# M_2_E-KEY.net
KiCad netlist of a schematic drawn in Altium Designer
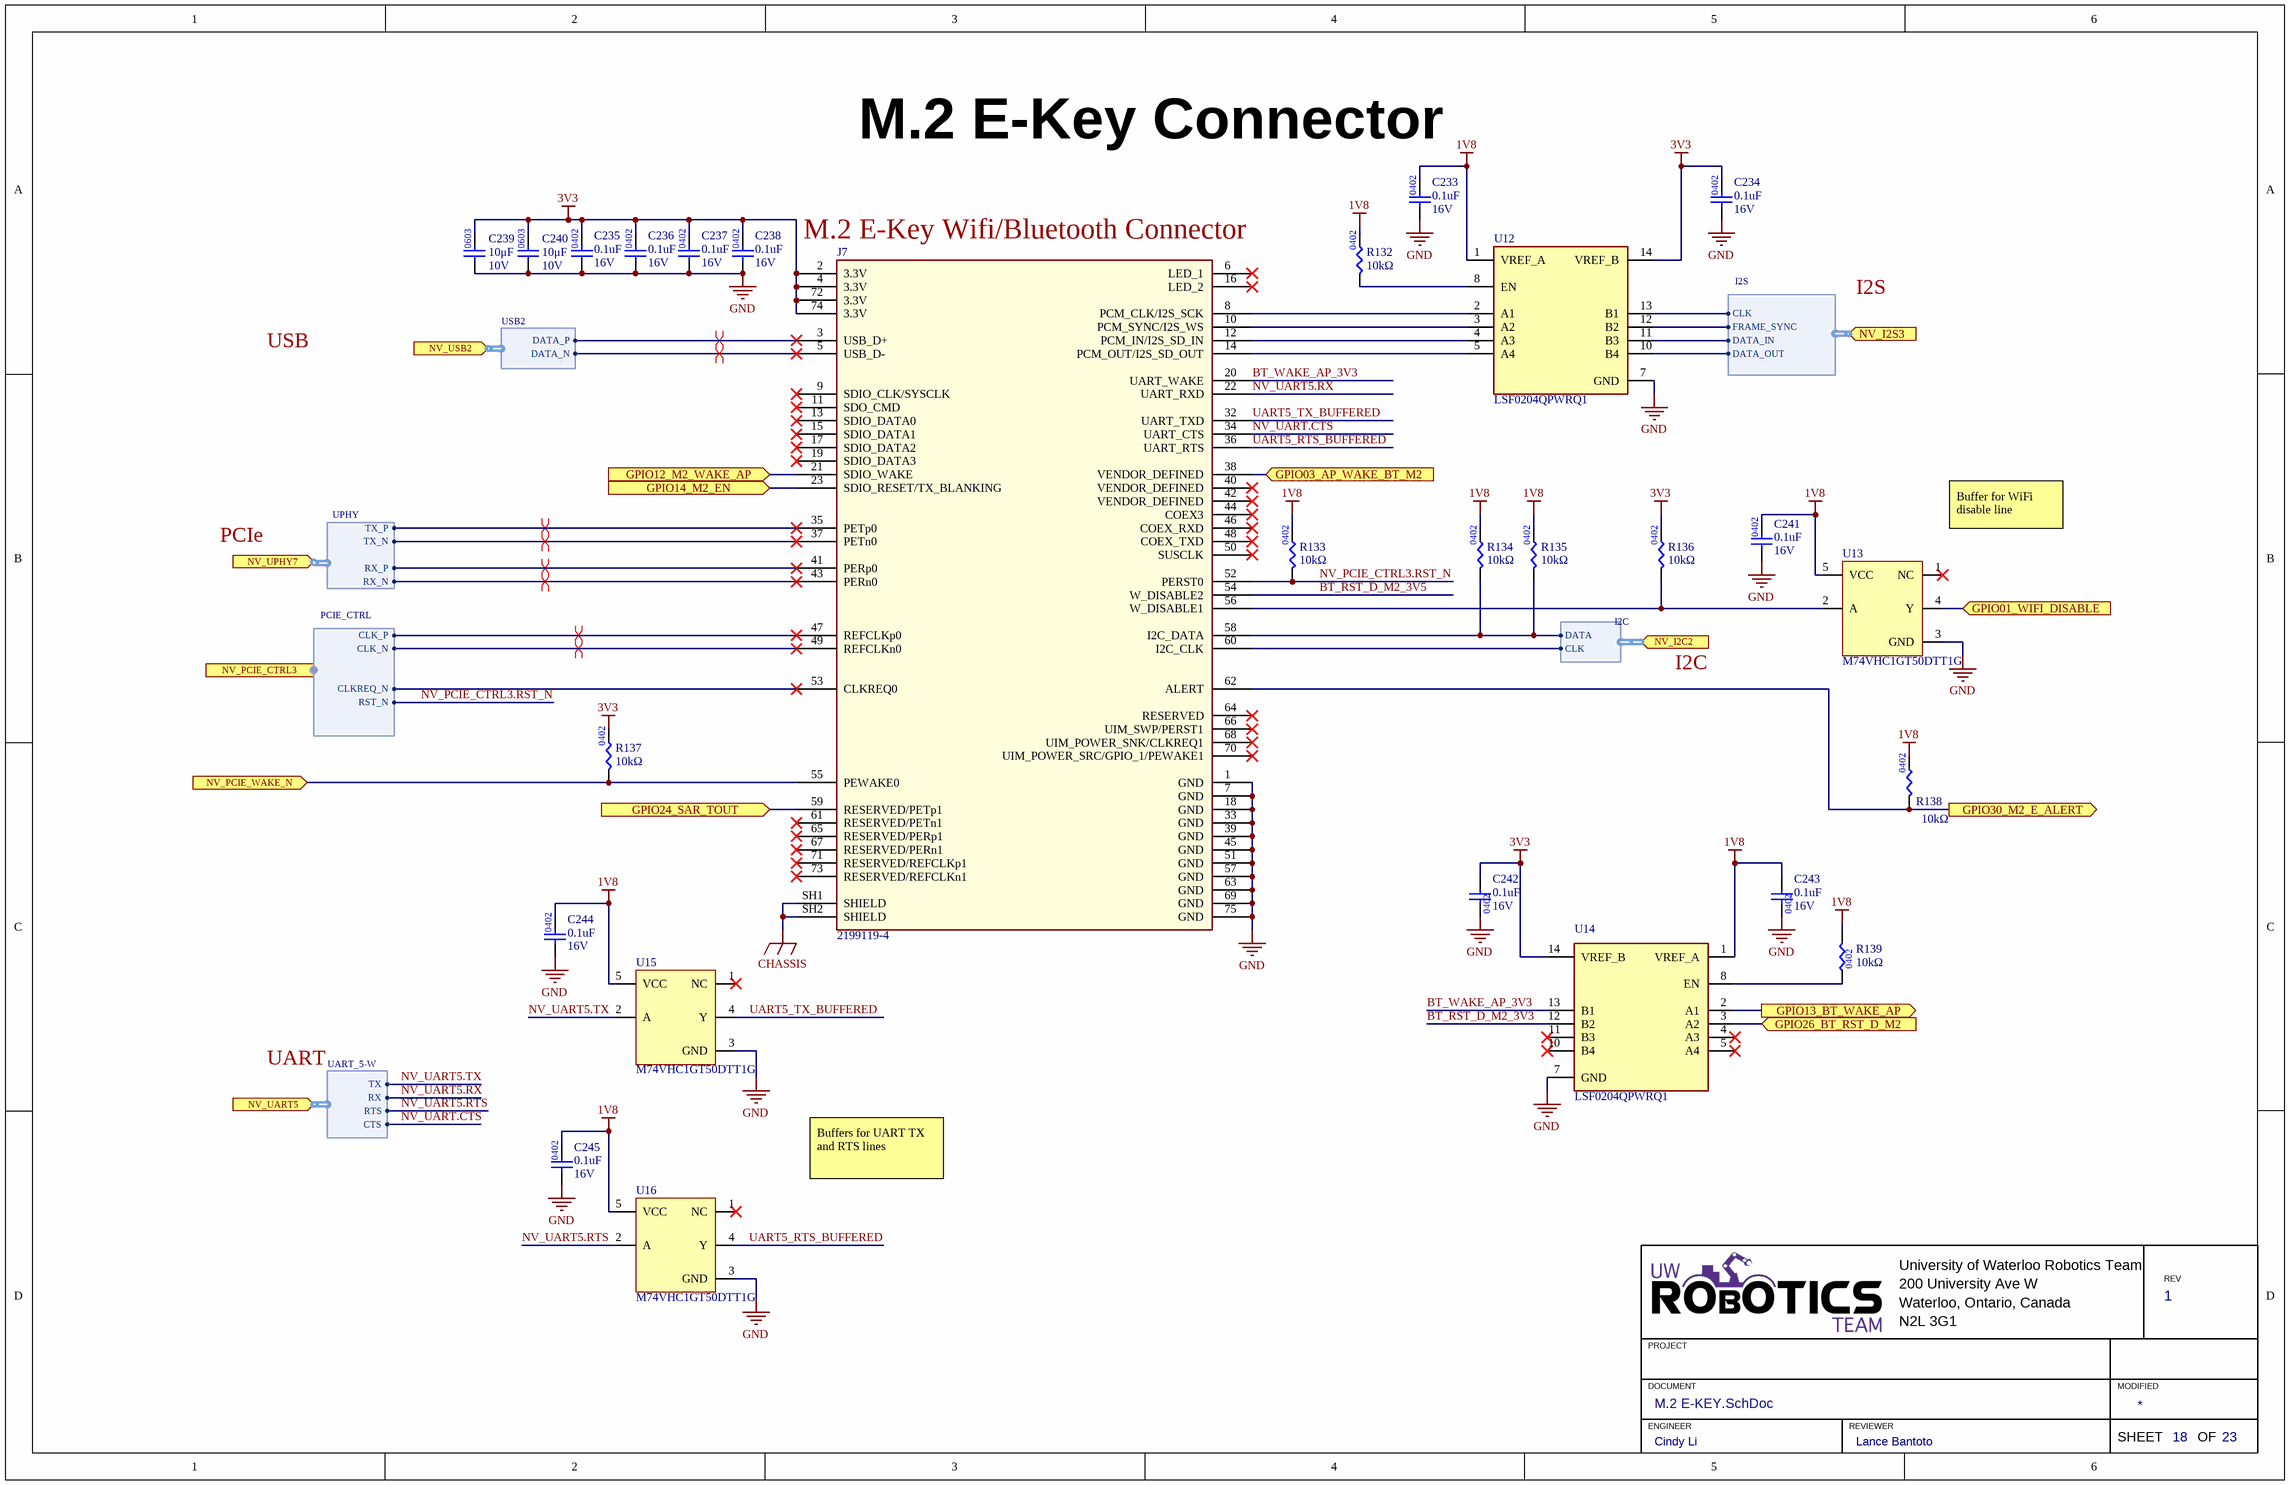
[diagram p0: M.2 E-KEY.SchDoc]

(export (version "E")
  (design (tool "Eeschema 10.0.6"))
  (components
    (comp (ref "C233")
      (value "CAP_0.1uF_16V_X7R_0402")
      (footprint "CAP0402")
      (description "CAP CER 0.1UF 16V X7R 0402")
      (fields (field (name "CAPACITANCE") "0.1uF") (field (name "VOLTAGE RATING") "16V"))
      (libsource (lib "UWRT_Schematic_Library_2020") (part "CAP_0.1uF_16V_X7R_0402"))
    )
    (comp (ref "C234")
      (value "CAP_0.1uF_16V_X7R_0402")
      (footprint "CAP0402")
      (description "CAP CER 0.1UF 16V X7R 0402")
      (fields (field (name "CAPACITANCE") "0.1uF") (field (name "VOLTAGE RATING") "16V"))
      (libsource (lib "UWRT_Schematic_Library_2020") (part "CAP_0.1uF_16V_X7R_0402"))
    )
    (comp (ref "C235")
      (value "CAP_0.1uF_16V_X7R_0402")
      (footprint "CAP0402")
      (description "CAP CER 0.1UF 16V X7R 0402")
      (fields (field (name "CAPACITANCE") "0.1uF") (field (name "VOLTAGE RATING") "16V"))
      (libsource (lib "UWRT_Schematic_Library_2020") (part "CAP_0.1uF_16V_X7R_0402"))
    )
    (comp (ref "C236")
      (value "CAP_0.1uF_16V_X7R_0402")
      (footprint "CAP0402")
      (description "CAP CER 0.1UF 16V X7R 0402")
      (fields (field (name "CAPACITANCE") "0.1uF") (field (name "VOLTAGE RATING") "16V"))
      (libsource (lib "UWRT_Schematic_Library_2020") (part "CAP_0.1uF_16V_X7R_0402"))
    )
    (comp (ref "C237")
      (value "CAP_0.1uF_16V_X7R_0402")
      (footprint "CAP0402")
      (description "CAP CER 0.1UF 16V X7R 0402")
      (fields (field (name "CAPACITANCE") "0.1uF") (field (name "VOLTAGE RATING") "16V"))
      (libsource (lib "UWRT_Schematic_Library_2020") (part "CAP_0.1uF_16V_X7R_0402"))
    )
    (comp (ref "C238")
      (value "CAP_0.1uF_16V_X7R_0402")
      (footprint "CAP0402")
      (description "CAP CER 0.1UF 16V X7R 0402")
      (fields (field (name "CAPACITANCE") "0.1uF") (field (name "VOLTAGE RATING") "16V"))
      (libsource (lib "UWRT_Schematic_Library_2020") (part "CAP_0.1uF_16V_X7R_0402"))
    )
    (comp (ref "C239")
      (value "10μF")
      (footprint "CAP0603")
      (description "CAP CER 10UF 10V X5R 0603")
      (fields (field (name "VOLTAGE RATING") "10V") (field (name "Comment") "CAP_10uF_10V_0603"))
      (libsource (lib "UWRT_Schematic_Library_2020") (part "CAP_10uF_10V_0603"))
    )
    (comp (ref "C240")
      (value "10μF")
      (footprint "CAP0603")
      (description "CAP CER 10UF 10V X5R 0603")
      (fields (field (name "VOLTAGE RATING") "10V") (field (name "Comment") "CAP_10uF_10V_0603"))
      (libsource (lib "UWRT_Schematic_Library_2020") (part "CAP_10uF_10V_0603"))
    )
    (comp (ref "C241")
      (value "CAP_0.1uF_16V_X7R_0402")
      (footprint "CAP0402")
      (description "CAP CER 0.1UF 16V X7R 0402")
      (fields (field (name "CAPACITANCE") "0.1uF") (field (name "VOLTAGE RATING") "16V"))
      (libsource (lib "UWRT_Schematic_Library_2020") (part "CAP_0.1uF_16V_X7R_0402"))
    )
    (comp (ref "C242")
      (value "CAP_0.1uF_16V_X7R_0402")
      (footprint "CAP0402")
      (description "CAP CER 0.1UF 16V X7R 0402")
      (fields (field (name "CAPACITANCE") "0.1uF") (field (name "VOLTAGE RATING") "16V"))
      (libsource (lib "UWRT_Schematic_Library_2020") (part "CAP_0.1uF_16V_X7R_0402"))
    )
    (comp (ref "C243")
      (value "CAP_0.1uF_16V_X7R_0402")
      (footprint "CAP0402")
      (description "CAP CER 0.1UF 16V X7R 0402")
      (fields (field (name "CAPACITANCE") "0.1uF") (field (name "VOLTAGE RATING") "16V"))
      (libsource (lib "UWRT_Schematic_Library_2020") (part "CAP_0.1uF_16V_X7R_0402"))
    )
    (comp (ref "C244")
      (value "CAP_0.1uF_16V_X7R_0402")
      (footprint "CAP0402")
      (description "CAP CER 0.1UF 16V X7R 0402")
      (fields (field (name "CAPACITANCE") "0.1uF") (field (name "VOLTAGE RATING") "16V"))
      (libsource (lib "UWRT_Schematic_Library_2020") (part "CAP_0.1uF_16V_X7R_0402"))
    )
    (comp (ref "C245")
      (value "CAP_0.1uF_16V_X7R_0402")
      (footprint "CAP0402")
      (description "CAP CER 0.1UF 16V X7R 0402")
      (fields (field (name "CAPACITANCE") "0.1uF") (field (name "VOLTAGE RATING") "16V"))
      (libsource (lib "UWRT_Schematic_Library_2020") (part "CAP_0.1uF_16V_X7R_0402"))
    )
    (comp (ref "J7")
      (value "2199119-4")
      (footprint "TE_2199119-4")
      (description "CONN M.2 FEMALE 67POS 0.020 GOLD")
      (fields (field (name "MANUFACTURER PART NUMBER 1") "2199119-4"))
      (libsource (lib "UWRT_Schematic_Library_2020") (part "2199119-4"))
    )
    (comp (ref "R132")
      (value "RES_10kΩ_0402_1%")
      (footprint "RES0402")
      (description "RES 10K OHM 1% 1/16W 0402")
      (fields (field (name "TOLERANCE") "1%") (field (name "RESISTANCE") "10kΩ"))
      (libsource (lib "UWRT_Schematic_Library_2020") (part "RES_10kΩ_0402_1%"))
    )
    (comp (ref "R133")
      (value "RES_10kΩ_0402_1%")
      (footprint "RES0402")
      (description "RES 10K OHM 1% 1/16W 0402")
      (fields (field (name "TOLERANCE") "1%") (field (name "RESISTANCE") "10kΩ"))
      (libsource (lib "UWRT_Schematic_Library_2020") (part "RES_10kΩ_0402_1%"))
    )
    (comp (ref "R134")
      (value "RES_10kΩ_0402_1%")
      (footprint "RES0402")
      (description "RES 10K OHM 1% 1/16W 0402")
      (fields (field (name "TOLERANCE") "1%") (field (name "RESISTANCE") "10kΩ"))
      (libsource (lib "UWRT_Schematic_Library_2020") (part "RES_10kΩ_0402_1%"))
    )
    (comp (ref "R135")
      (value "RES_10kΩ_0402_1%")
      (footprint "RES0402")
      (description "RES 10K OHM 1% 1/16W 0402")
      (fields (field (name "TOLERANCE") "1%") (field (name "RESISTANCE") "10kΩ"))
      (libsource (lib "UWRT_Schematic_Library_2020") (part "RES_10kΩ_0402_1%"))
    )
    (comp (ref "R136")
      (value "RES_10kΩ_0402_1%")
      (footprint "RES0402")
      (description "RES 10K OHM 1% 1/16W 0402")
      (fields (field (name "TOLERANCE") "1%") (field (name "RESISTANCE") "10kΩ"))
      (libsource (lib "UWRT_Schematic_Library_2020") (part "RES_10kΩ_0402_1%"))
    )
    (comp (ref "R137")
      (value "RES_10kΩ_0402_1%")
      (footprint "RES0402")
      (description "RES 10K OHM 1% 1/16W 0402")
      (fields (field (name "TOLERANCE") "1%") (field (name "RESISTANCE") "10kΩ"))
      (libsource (lib "UWRT_Schematic_Library_2020") (part "RES_10kΩ_0402_1%"))
    )
    (comp (ref "R138")
      (value "RES_10kΩ_0402_1%")
      (footprint "RES0402")
      (description "RES 10K OHM 1% 1/16W 0402")
      (fields (field (name "TOLERANCE") "1%") (field (name "RESISTANCE") "10kΩ"))
      (libsource (lib "UWRT_Schematic_Library_2020") (part "RES_10kΩ_0402_1%"))
    )
    (comp (ref "R139")
      (value "RES_10kΩ_0402_1%")
      (footprint "RES0402")
      (description "RES 10K OHM 1% 1/16W 0402")
      (fields (field (name "TOLERANCE") "1%") (field (name "RESISTANCE") "10kΩ"))
      (libsource (lib "UWRT_Schematic_Library_2020") (part "RES_10kΩ_0402_1%"))
    )
    (comp (ref "U12")
      (value "LSF0204QPWRQ1")
      (footprint "14-TSSOP")
      (description "4-BITS MULTI-VOLTAGE LEVEL TRANS")
      (libsource (lib "UWRT_Schematic_Library_2020") (part "LSF0204QPWRQ1"))
    )
    (comp (ref "U13")
      (value "IC_BUFFER")
      (footprint "SOT23-5")
      (description "IC BUFFER NON-INVERT 5.5V 5TSOP")
      (fields (field (name "MANUFACTURER PART NUMBER 1") "M74VHC1GT50DTT1G"))
      (libsource (lib "UWRT_Schematic_Library_2020") (part "IC_BUFFER"))
    )
    (comp (ref "U14")
      (value "LSF0204QPWRQ1")
      (footprint "14-TSSOP")
      (description "4-BITS MULTI-VOLTAGE LEVEL TRANS")
      (libsource (lib "") (part "LSF0204QPWRQ1_1"))
    )
    (comp (ref "U15")
      (value "IC_BUFFER")
      (footprint "SOT23-5")
      (description "IC BUFFER NON-INVERT 5.5V 5TSOP")
      (fields (field (name "MANUFACTURER PART NUMBER 1") "M74VHC1GT50DTT1G"))
      (libsource (lib "UWRT_Schematic_Library_2020") (part "IC_BUFFER"))
    )
    (comp (ref "U16")
      (value "IC_BUFFER")
      (footprint "SOT23-5")
      (description "IC BUFFER NON-INVERT 5.5V 5TSOP")
      (fields (field (name "MANUFACTURER PART NUMBER 1") "M74VHC1GT50DTT1G"))
      (libsource (lib "UWRT_Schematic_Library_2020") (part "IC_BUFFER"))
    )
  )
  (nets
    (net (code "7") (name "/BT_RST_D_M2_3V3") (class "Default")
      (node (ref "U14") (pin "12") (pinfunction "B2_12") (pintype "passive"))
    )
    (net (code "8") (name "/BT_RST_D_M2_3V5") (class "Default")
      (node (ref "J7") (pin "54") (pinfunction "W_DISABLE2_54") (pintype "passive"))
    )
    (net (code "9") (name "/BT_WAKE_AP_3V3") (class "Default")
      (node (ref "J7") (pin "20") (pinfunction "UART_WAKE_20") (pintype "passive"))
      (node (ref "U14") (pin "13") (pinfunction "B1_13") (pintype "passive"))
    )
    (net (code "10") (name "/CLKREQ_N") (class "Default")
      (node (ref "J7") (pin "53") (pinfunction "CLKREQ0_53") (pintype "passive+no_connect"))
    )
    (net (code "11") (name "/CLK_N") (class "Default")
      (node (ref "J7") (pin "49") (pinfunction "REFCLKn0_49") (pintype "passive+no_connect"))
    )
    (net (code "12") (name "/CLK_P") (class "Default")
      (node (ref "J7") (pin "47") (pinfunction "REFCLKp0_47") (pintype "passive+no_connect"))
    )
    (net (code "13") (name "/DATA") (class "Default")
      (node (ref "J7") (pin "58") (pinfunction "I2C_DATA_58") (pintype "passive"))
      (node (ref "R134") (pin "1") (pinfunction "1_1") (pintype "passive"))
      (node (ref "R135") (pin "1") (pinfunction "1_1") (pintype "passive"))
    )
    (net (code "14") (name "/DATA_IN") (class "Default")
      (node (ref "U12") (pin "11") (pinfunction "B3_11") (pintype "passive"))
    )
    (net (code "15") (name "/DATA_N") (class "Default")
      (node (ref "J7") (pin "5") (pinfunction "USB_D-_5") (pintype "passive+no_connect"))
    )
    (net (code "16") (name "/DATA_OUT") (class "Default")
      (node (ref "U12") (pin "10") (pinfunction "B4_10") (pintype "passive"))
    )
    (net (code "17") (name "/DATA_P") (class "Default")
      (node (ref "J7") (pin "3") (pinfunction "USB_D+_3") (pintype "passive+no_connect"))
    )
    (net (code "18") (name "/FRAME_SYNC") (class "Default")
      (node (ref "U12") (pin "12") (pinfunction "B2_12") (pintype "passive"))
    )
    (net (code "19") (name "/GPIO01_WIFI_DISABLE") (class "Default")
      (node (ref "U13") (pin "4") (pinfunction "Y_4") (pintype "passive"))
    )
    (net (code "20") (name "/GPIO03_AP_WAKE_BT_M2") (class "Default")
      (node (ref "J7") (pin "38") (pinfunction "VENDOR_DEFINED_38") (pintype "passive"))
    )
    (net (code "21") (name "/GPIO12_M2_WAKE_AP") (class "Default")
      (node (ref "J7") (pin "21") (pinfunction "SDIO_WAKE_21") (pintype "passive"))
    )
    (net (code "22") (name "/GPIO13_BT_WAKE_AP") (class "Default")
      (node (ref "U14") (pin "2") (pinfunction "A1_2") (pintype "passive"))
    )
    (net (code "23") (name "/GPIO14_M2_EN") (class "Default")
      (node (ref "J7") (pin "23") (pinfunction "SDIO_RESET/TX_BLANKING_23") (pintype "passive"))
    )
    (net (code "24") (name "/GPIO24_SAR_TOUT") (class "Default")
      (node (ref "J7") (pin "59") (pinfunction "RESERVED/PETp1_59") (pintype "passive"))
    )
    (net (code "25") (name "/GPIO26_BT_RST_D_M2") (class "Default")
      (node (ref "U14") (pin "3") (pinfunction "A2_3") (pintype "passive"))
    )
    (net (code "26") (name "/GPIO30_M2_E_ALERT") (class "Default")
      (node (ref "J7") (pin "62") (pinfunction "ALERT_62") (pintype "passive"))
      (node (ref "R138") (pin "1") (pinfunction "1_1") (pintype "passive"))
    )
    (net (code "27") (name "/NV_PCIE_CTRL3.RST_N") (class "Default")
      (node (ref "J7") (pin "52") (pinfunction "PERST0_52") (pintype "passive"))
      (node (ref "R133") (pin "1") (pinfunction "1_1") (pintype "passive"))
    )
    (net (code "28") (name "/NV_PCIE_WAKE_N") (class "Default")
      (node (ref "J7") (pin "55") (pinfunction "PEWAKE0_55") (pintype "passive"))
      (node (ref "R137") (pin "1") (pinfunction "1_1") (pintype "passive"))
    )
    (net (code "29") (name "/NV_UART.CTS") (class "Default")
      (node (ref "J7") (pin "34") (pinfunction "UART_CTS_34") (pintype "passive"))
    )
    (net (code "30") (name "/NV_UART5.RTS") (class "Default")
      (node (ref "U16") (pin "2") (pinfunction "A_2") (pintype "passive"))
    )
    (net (code "31") (name "/NV_UART5.RX") (class "Default")
      (node (ref "J7") (pin "22") (pinfunction "UART_RXD_22") (pintype "passive"))
    )
    (net (code "32") (name "/NV_UART5.TX") (class "Default")
      (node (ref "U15") (pin "2") (pinfunction "A_2") (pintype "passive"))
    )
    (net (code "33") (name "/RX_N") (class "Default")
      (node (ref "J7") (pin "43") (pinfunction "PERn0_43") (pintype "passive+no_connect"))
    )
    (net (code "34") (name "/RX_P") (class "Default")
      (node (ref "J7") (pin "41") (pinfunction "PERp0_41") (pintype "passive+no_connect"))
    )
    (net (code "35") (name "/TX_N") (class "Default")
      (node (ref "J7") (pin "37") (pinfunction "PETn0_37") (pintype "passive+no_connect"))
    )
    (net (code "36") (name "/TX_P") (class "Default")
      (node (ref "J7") (pin "35") (pinfunction "PETp0_35") (pintype "passive+no_connect"))
    )
    (net (code "37") (name "/UART5_RTS_BUFFERED") (class "Default")
      (node (ref "J7") (pin "36") (pinfunction "UART_RTS_36") (pintype "passive"))
      (node (ref "U16") (pin "4") (pinfunction "Y_4") (pintype "passive"))
    )
    (net (code "38") (name "/UART5_TX_BUFFERED") (class "Default")
      (node (ref "J7") (pin "32") (pinfunction "UART_TXD_32") (pintype "passive"))
      (node (ref "U15") (pin "4") (pinfunction "Y_4") (pintype "passive"))
    )
    (net (code "45") (name "1V8") (class "Default")
      (node (ref "C233") (pin "2") (pinfunction "2_2") (pintype "passive"))
      (node (ref "C241") (pin "2") (pinfunction "2_2") (pintype "passive"))
      (node (ref "C243") (pin "2") (pinfunction "2_2") (pintype "passive"))
      (node (ref "C244") (pin "2") (pinfunction "2_2") (pintype "passive"))
      (node (ref "C245") (pin "2") (pinfunction "2_2") (pintype "passive"))
      (node (ref "R132") (pin "2") (pinfunction "2_2") (pintype "passive"))
      (node (ref "R133") (pin "2") (pinfunction "2_2") (pintype "passive"))
      (node (ref "R134") (pin "2") (pinfunction "2_2") (pintype "passive"))
      (node (ref "R135") (pin "2") (pinfunction "2_2") (pintype "passive"))
      (node (ref "R138") (pin "2") (pinfunction "2_2") (pintype "passive"))
      (node (ref "R139") (pin "2") (pinfunction "2_2") (pintype "passive"))
      (node (ref "U12") (pin "1") (pinfunction "VREF_A_1") (pintype "passive"))
      (node (ref "U13") (pin "5") (pinfunction "VCC_5") (pintype "passive"))
      (node (ref "U14") (pin "1") (pinfunction "VREF_A_1") (pintype "passive"))
      (node (ref "U15") (pin "5") (pinfunction "VCC_5") (pintype "passive"))
      (node (ref "U16") (pin "5") (pinfunction "VCC_5") (pintype "passive"))
    )
    (net (code "46") (name "3V3") (class "Default")
      (node (ref "C234") (pin "2") (pinfunction "2_2") (pintype "passive"))
      (node (ref "C235") (pin "2") (pinfunction "2_2") (pintype "passive"))
      (node (ref "C236") (pin "2") (pinfunction "2_2") (pintype "passive"))
      (node (ref "C237") (pin "2") (pinfunction "2_2") (pintype "passive"))
      (node (ref "C238") (pin "2") (pinfunction "2_2") (pintype "passive"))
      (node (ref "C239") (pin "2") (pinfunction "2_2") (pintype "passive"))
      (node (ref "C240") (pin "2") (pinfunction "2_2") (pintype "passive"))
      (node (ref "C242") (pin "2") (pinfunction "2_2") (pintype "passive"))
      (node (ref "J7") (pin "2") (pinfunction "3.3V_2") (pintype "passive"))
      (node (ref "J7") (pin "4") (pinfunction "3.3V_4") (pintype "passive"))
      (node (ref "J7") (pin "72") (pinfunction "3.3V_72") (pintype "passive"))
      (node (ref "J7") (pin "74") (pinfunction "3.3V_74") (pintype "passive"))
      (node (ref "R136") (pin "2") (pinfunction "2_2") (pintype "passive"))
      (node (ref "R137") (pin "2") (pinfunction "2_2") (pintype "passive"))
      (node (ref "U12") (pin "14") (pinfunction "VREF_B_14") (pintype "passive"))
      (node (ref "U14") (pin "14") (pinfunction "VREF_B_14") (pintype "passive"))
    )
    (net (code "47") (name "CHASSIS") (class "Default")
      (node (ref "J7") (pin "SH1") (pinfunction "SHIELD_SH1") (pintype "passive"))
      (node (ref "J7") (pin "SH2") (pinfunction "SHIELD_SH2") (pintype "passive"))
    )
    (net (code "48") (name "GND") (class "Default")
      (node (ref "C233") (pin "1") (pinfunction "1_1") (pintype "passive"))
      (node (ref "C234") (pin "1") (pinfunction "1_1") (pintype "passive"))
      (node (ref "C235") (pin "1") (pinfunction "1_1") (pintype "passive"))
      (node (ref "C236") (pin "1") (pinfunction "1_1") (pintype "passive"))
      (node (ref "C237") (pin "1") (pinfunction "1_1") (pintype "passive"))
      (node (ref "C238") (pin "1") (pinfunction "1_1") (pintype "passive"))
      (node (ref "C239") (pin "1") (pinfunction "1_1") (pintype "passive"))
      (node (ref "C240") (pin "1") (pinfunction "1_1") (pintype "passive"))
      (node (ref "C241") (pin "1") (pinfunction "1_1") (pintype "passive"))
      (node (ref "C242") (pin "1") (pinfunction "1_1") (pintype "passive"))
      (node (ref "C243") (pin "1") (pinfunction "1_1") (pintype "passive"))
      (node (ref "C244") (pin "1") (pinfunction "1_1") (pintype "passive"))
      (node (ref "C245") (pin "1") (pinfunction "1_1") (pintype "passive"))
      (node (ref "J7") (pin "1") (pinfunction "GND_1") (pintype "passive"))
      (node (ref "J7") (pin "18") (pinfunction "GND_18") (pintype "passive"))
      (node (ref "J7") (pin "33") (pinfunction "GND_33") (pintype "passive"))
      (node (ref "J7") (pin "39") (pinfunction "GND_39") (pintype "passive"))
      (node (ref "J7") (pin "45") (pinfunction "GND_45") (pintype "passive"))
      (node (ref "J7") (pin "51") (pinfunction "GND_51") (pintype "passive"))
      (node (ref "J7") (pin "57") (pinfunction "GND_57") (pintype "passive"))
      (node (ref "J7") (pin "63") (pinfunction "GND_63") (pintype "passive"))
      (node (ref "J7") (pin "69") (pinfunction "GND_69") (pintype "passive"))
      (node (ref "J7") (pin "7") (pinfunction "GND_7") (pintype "passive"))
      (node (ref "J7") (pin "75") (pinfunction "GND_75") (pintype "passive"))
      (node (ref "U12") (pin "7") (pinfunction "GND_7") (pintype "passive"))
      (node (ref "U13") (pin "3") (pinfunction "GND_3") (pintype "passive"))
      (node (ref "U14") (pin "7") (pinfunction "GND_7") (pintype "passive"))
      (node (ref "U15") (pin "3") (pinfunction "GND_3") (pintype "passive"))
      (node (ref "U16") (pin "3") (pinfunction "GND_3") (pintype "passive"))
    )
    (net (code "49") (name "Net-(J7-PCM_CLK{slash}I2S_SCK)") (class "Default")
      (node (ref "J7") (pin "8") (pinfunction "PCM_CLK/I2S_SCK_8") (pintype "passive"))
      (node (ref "U12") (pin "2") (pinfunction "A1_2") (pintype "passive"))
    )
    (net (code "50") (name "Net-(J7-PCM_IN{slash}I2S_SD_IN)") (class "Default")
      (node (ref "J7") (pin "12") (pinfunction "PCM_IN/I2S_SD_IN_12") (pintype "passive"))
      (node (ref "U12") (pin "4") (pinfunction "A3_4") (pintype "passive"))
    )
    (net (code "51") (name "Net-(J7-PCM_OUT{slash}I2S_SD_OUT)") (class "Default")
      (node (ref "J7") (pin "14") (pinfunction "PCM_OUT/I2S_SD_OUT_14") (pintype "passive"))
      (node (ref "U12") (pin "5") (pinfunction "A4_5") (pintype "passive"))
    )
    (net (code "52") (name "Net-(J7-PCM_SYNC{slash}I2S_WS)") (class "Default")
      (node (ref "J7") (pin "10") (pinfunction "PCM_SYNC/I2S_WS_10") (pintype "passive"))
      (node (ref "U12") (pin "3") (pinfunction "A2_3") (pintype "passive"))
    )
    (net (code "53") (name "Net-(J7-W_DISABLE1)") (class "Default")
      (node (ref "J7") (pin "56") (pinfunction "W_DISABLE1_56") (pintype "passive"))
      (node (ref "R136") (pin "1") (pinfunction "1_1") (pintype "passive"))
      (node (ref "U13") (pin "2") (pinfunction "A_2") (pintype "passive"))
    )
    (net (code "54") (name "Net-(U12-EN)") (class "Default")
      (node (ref "R132") (pin "1") (pinfunction "1_1") (pintype "passive"))
      (node (ref "U12") (pin "8") (pinfunction "EN_8") (pintype "passive"))
    )
    (net (code "55") (name "Net-(U14-EN)") (class "Default")
      (node (ref "R139") (pin "1") (pinfunction "1_1") (pintype "passive"))
      (node (ref "U14") (pin "8") (pinfunction "EN_8") (pintype "passive"))
    )
    (net (code "56") (name "unconnected-(J7-COEX3-Pad44)") (class "Default")
      (node (ref "J7") (pin "44") (pinfunction "COEX3_44") (pintype "passive+no_connect"))
    )
    (net (code "57") (name "unconnected-(J7-COEX_RXD-Pad46)") (class "Default")
      (node (ref "J7") (pin "46") (pinfunction "COEX_RXD_46") (pintype "passive+no_connect"))
    )
    (net (code "58") (name "unconnected-(J7-COEX_TXD-Pad48)") (class "Default")
      (node (ref "J7") (pin "48") (pinfunction "COEX_TXD_48") (pintype "passive+no_connect"))
    )
    (net (code "59") (name "unconnected-(J7-I2C_CLK-Pad60)") (class "Default")
      (node (ref "J7") (pin "60") (pinfunction "I2C_CLK_60") (pintype "passive"))
    )
    (net (code "60") (name "unconnected-(J7-LED_1-Pad6)") (class "Default")
      (node (ref "J7") (pin "6") (pinfunction "LED_1_6") (pintype "passive+no_connect"))
    )
    (net (code "61") (name "unconnected-(J7-LED_2-Pad16)") (class "Default")
      (node (ref "J7") (pin "16") (pinfunction "LED_2_16") (pintype "passive+no_connect"))
    )
    (net (code "62") (name "unconnected-(J7-RESERVED-Pad64)") (class "Default")
      (node (ref "J7") (pin "64") (pinfunction "RESERVED_64") (pintype "passive+no_connect"))
    )
    (net (code "63") (name "unconnected-(J7-RESERVED{slash}PERn1-Pad67)") (class "Default")
      (node (ref "J7") (pin "67") (pinfunction "RESERVED/PERn1_67") (pintype "passive+no_connect"))
    )
    (net (code "64") (name "unconnected-(J7-RESERVED{slash}PERp1-Pad65)") (class "Default")
      (node (ref "J7") (pin "65") (pinfunction "RESERVED/PERp1_65") (pintype "passive+no_connect"))
    )
    (net (code "65") (name "unconnected-(J7-RESERVED{slash}PETn1-Pad61)") (class "Default")
      (node (ref "J7") (pin "61") (pinfunction "RESERVED/PETn1_61") (pintype "passive+no_connect"))
    )
    (net (code "66") (name "unconnected-(J7-RESERVED{slash}REFCLKn1-Pad73)") (class "Default")
      (node (ref "J7") (pin "73") (pinfunction "RESERVED/REFCLKn1_73") (pintype "passive+no_connect"))
    )
    (net (code "67") (name "unconnected-(J7-RESERVED{slash}REFCLKp1-Pad71)") (class "Default")
      (node (ref "J7") (pin "71") (pinfunction "RESERVED/REFCLKp1_71") (pintype "passive+no_connect"))
    )
    (net (code "68") (name "unconnected-(J7-SDIO_CLK{slash}SYSCLK-Pad9)") (class "Default")
      (node (ref "J7") (pin "9") (pinfunction "SDIO_CLK/SYSCLK_9") (pintype "passive+no_connect"))
    )
    (net (code "69") (name "unconnected-(J7-SDIO_DATA0-Pad13)") (class "Default")
      (node (ref "J7") (pin "13") (pinfunction "SDIO_DATA0_13") (pintype "passive+no_connect"))
    )
    (net (code "70") (name "unconnected-(J7-SDIO_DATA1-Pad15)") (class "Default")
      (node (ref "J7") (pin "15") (pinfunction "SDIO_DATA1_15") (pintype "passive+no_connect"))
    )
    (net (code "71") (name "unconnected-(J7-SDIO_DATA2-Pad17)") (class "Default")
      (node (ref "J7") (pin "17") (pinfunction "SDIO_DATA2_17") (pintype "passive+no_connect"))
    )
    (net (code "72") (name "unconnected-(J7-SDIO_DATA3-Pad19)") (class "Default")
      (node (ref "J7") (pin "19") (pinfunction "SDIO_DATA3_19") (pintype "passive+no_connect"))
    )
    (net (code "73") (name "unconnected-(J7-SDO_CMD-Pad11)") (class "Default")
      (node (ref "J7") (pin "11") (pinfunction "SDO_CMD_11") (pintype "passive+no_connect"))
    )
    (net (code "74") (name "unconnected-(J7-SUSCLK-Pad50)") (class "Default")
      (node (ref "J7") (pin "50") (pinfunction "SUSCLK_50") (pintype "passive+no_connect"))
    )
    (net (code "75") (name "unconnected-(J7-UIM_POWER_SNK{slash}CLKREQ1-Pad68)") (class "Default")
      (node (ref "J7") (pin "68") (pinfunction "UIM_POWER_SNK/CLKREQ1_68") (pintype "passive+no_connect"))
    )
    (net (code "76") (name "unconnected-(J7-UIM_POWER_SRC{slash}GPIO_1{slash}PEWAKE1-Pad70)") (class "Default")
      (node (ref "J7") (pin "70") (pinfunction "UIM_POWER_SRC/GPIO_1/PEWAKE1_70") (pintype "passive+no_connect"))
    )
    (net (code "77") (name "unconnected-(J7-UIM_SWP{slash}PERST1-Pad66)") (class "Default")
      (node (ref "J7") (pin "66") (pinfunction "UIM_SWP/PERST1_66") (pintype "passive+no_connect"))
    )
    (net (code "78") (name "unconnected-(J7-VENDOR_DEFINED-Pad40)") (class "Default")
      (node (ref "J7") (pin "40") (pinfunction "VENDOR_DEFINED_40") (pintype "passive+no_connect"))
    )
    (net (code "79") (name "unconnected-(J7-VENDOR_DEFINED-Pad42)") (class "Default")
      (node (ref "J7") (pin "42") (pinfunction "VENDOR_DEFINED_42") (pintype "passive+no_connect"))
    )
    (net (code "80") (name "unconnected-(U12-B1-Pad13)") (class "Default")
      (node (ref "U12") (pin "13") (pinfunction "B1_13") (pintype "passive"))
    )
    (net (code "81") (name "unconnected-(U13-NC-Pad1)") (class "Default")
      (node (ref "U13") (pin "1") (pinfunction "NC_1") (pintype "passive+no_connect"))
    )
    (net (code "82") (name "unconnected-(U14-A3-Pad4)") (class "Default")
      (node (ref "U14") (pin "4") (pinfunction "A3_4") (pintype "passive+no_connect"))
    )
    (net (code "83") (name "unconnected-(U14-A4-Pad5)") (class "Default")
      (node (ref "U14") (pin "5") (pinfunction "A4_5") (pintype "passive+no_connect"))
    )
    (net (code "84") (name "unconnected-(U14-B3-Pad11)") (class "Default")
      (node (ref "U14") (pin "11") (pinfunction "B3_11") (pintype "passive+no_connect"))
    )
    (net (code "85") (name "unconnected-(U14-B4-Pad10)") (class "Default")
      (node (ref "U14") (pin "10") (pinfunction "B4_10") (pintype "passive+no_connect"))
    )
    (net (code "86") (name "unconnected-(U15-NC-Pad1)") (class "Default")
      (node (ref "U15") (pin "1") (pinfunction "NC_1") (pintype "passive+no_connect"))
    )
    (net (code "87") (name "unconnected-(U16-NC-Pad1)") (class "Default")
      (node (ref "U16") (pin "1") (pinfunction "NC_1") (pintype "passive+no_connect"))
    )
  )
)
